# Occupancy_PCB_Final_Rev_B.net
KiCad netlist of a schematic drawn in EAGLE
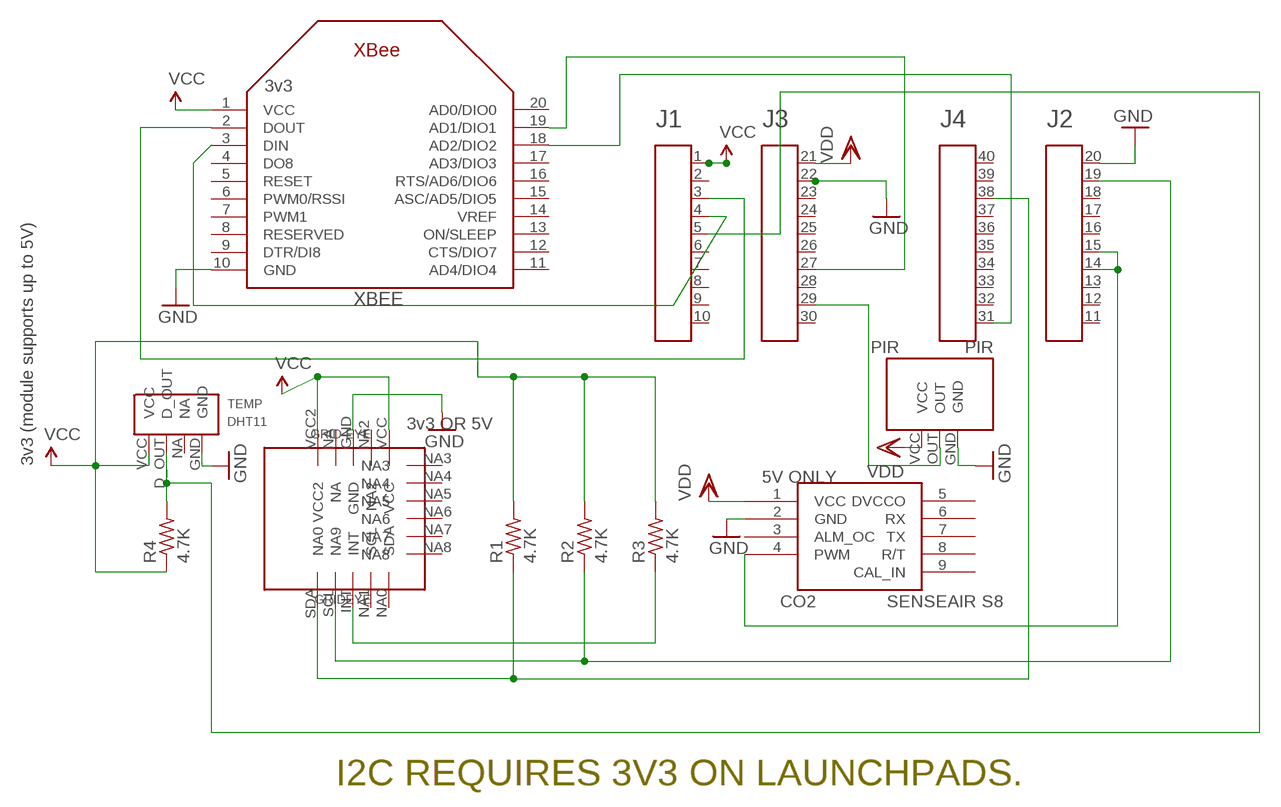
[diagram p0: schematic, sheet 1]

(export (version "E")
  (design (tool "Eeschema 10.0.6"))
  (components
    (comp (ref "CO2")
      (value "SENSEAIR-S8-DIP")
      (footprint "eagle-import:SENSEAIR-S8-DIP")
      (libsource (lib "eagle-import") (part "SENSEAIR-S8-DIP"))
    )
    (comp (ref "GRIDEYE")
      (value "GRID-EYE-DIP")
      (footprint "eagle-import:GRID-EYE-DIP")
      (libsource (lib "eagle-import") (part "GRID-EYE-DIP"))
    )
    (comp (ref "LAUNCHPAD")
      (value "HEADER4X10-BOOSTERPACK")
      (footprint "eagle-import:4X10-BOOSTERPACK")
      (libsource (lib "eagle-import") (part "HEADER4X10-BOOSTERPACK"))
    )
    (comp (ref "PIR")
      (value "PIR-DIP")
      (footprint "eagle-import:PIR-DIP")
      (libsource (lib "eagle-import") (part "PIR-DIP"))
    )
    (comp (ref "R1")
      (value "4.7K")
      (footprint "eagle-import:R0805")
      (libsource (lib "eagle-import") (part "R-US_R0805"))
    )
    (comp (ref "R2")
      (value "4.7K")
      (footprint "eagle-import:R0805")
      (libsource (lib "eagle-import") (part "R-US_R0805"))
    )
    (comp (ref "R3")
      (value "4.7K")
      (footprint "eagle-import:R0805")
      (libsource (lib "eagle-import") (part "R-US_R0805"))
    )
    (comp (ref "R4")
      (value "4.7K")
      (footprint "eagle-import:R0805")
      (libsource (lib "eagle-import") (part "R-US_R0805"))
    )
    (comp (ref "TEMP")
      (value "DHT11-DIP")
      (footprint "eagle-import:DHT11-DIP")
      (libsource (lib "eagle-import") (part "DHT11-DIP"))
    )
    (comp (ref "XBEE")
      (value "XBEE")
      (footprint "eagle-import:XBEE")
      (libsource (lib "eagle-import") (part "XBEE"))
    )
  )
  (nets
    (net (code "1") (name "GND") (class "Default")
      (node (ref "CO2") (pin "2") (pinfunction "GND_2") (pintype "bidirectional"))
      (node (ref "GRIDEYE") (pin "GND") (pinfunction "GND_GND") (pintype "bidirectional"))
      (node (ref "LAUNCHPAD") (pin "20") (pinfunction "P$20_20") (pintype "bidirectional"))
      (node (ref "LAUNCHPAD") (pin "22") (pinfunction "P$22_22") (pintype "bidirectional"))
      (node (ref "PIR") (pin "GND") (pinfunction "GND_GND") (pintype "bidirectional"))
      (node (ref "TEMP") (pin "GND") (pinfunction "GND_GND") (pintype "bidirectional"))
      (node (ref "XBEE") (pin "10") (pinfunction "GND_10") (pintype "power_in"))
    )
    (net (code "2") (name "Net-(CO2-PWM)") (class "Default")
      (node (ref "CO2") (pin "4") (pinfunction "PWM_4") (pintype "bidirectional"))
      (node (ref "LAUNCHPAD") (pin "14") (pinfunction "P$14_14") (pintype "bidirectional"))
      (node (ref "LAUNCHPAD") (pin "15") (pinfunction "P$15_15") (pintype "bidirectional"))
    )
    (net (code "3") (name "Net-(GRIDEYE-NA0)") (class "Default")
      (node (ref "GRIDEYE") (pin "SDA") (pinfunction "NA0_SDA") (pintype "bidirectional"))
      (node (ref "LAUNCHPAD") (pin "38") (pinfunction "P$38_38") (pintype "bidirectional"))
      (node (ref "R1") (pin "1") (pinfunction "1_1") (pintype "passive"))
    )
    (net (code "4") (name "Net-(GRIDEYE-NA9)") (class "Default")
      (node (ref "GRIDEYE") (pin "SCL") (pinfunction "NA9_SCL") (pintype "bidirectional"))
      (node (ref "LAUNCHPAD") (pin "19") (pinfunction "P$19_19") (pintype "bidirectional"))
      (node (ref "R2") (pin "1") (pinfunction "1_1") (pintype "passive"))
    )
    (net (code "5") (name "Net-(GRIDEYE-PadINT)") (class "Default")
      (node (ref "GRIDEYE") (pin "INT") (pinfunction "INT_INT") (pintype "bidirectional"))
      (node (ref "R3") (pin "1") (pinfunction "1_1") (pintype "passive"))
    )
    (net (code "6") (name "Net-(LAUNCHPAD-P$3)") (class "Default")
      (node (ref "LAUNCHPAD") (pin "3") (pinfunction "P$3_3") (pintype "bidirectional"))
      (node (ref "XBEE") (pin "2") (pinfunction "DOUT_2") (pintype "output"))
    )
    (net (code "7") (name "Net-(LAUNCHPAD-P$4)") (class "Default")
      (node (ref "LAUNCHPAD") (pin "4") (pinfunction "P$4_4") (pintype "bidirectional"))
      (node (ref "XBEE") (pin "3") (pinfunction "DIN_3") (pintype "input"))
    )
    (net (code "8") (name "Net-(LAUNCHPAD-P$5)") (class "Default")
      (node (ref "LAUNCHPAD") (pin "5") (pinfunction "P$5_5") (pintype "bidirectional"))
      (node (ref "R4") (pin "2") (pinfunction "2_2") (pintype "passive"))
      (node (ref "TEMP") (pin "D_OUT") (pinfunction "D_OUT_D_OUT") (pintype "bidirectional"))
    )
    (net (code "9") (name "Net-(LAUNCHPAD-P$27)") (class "Default")
      (node (ref "LAUNCHPAD") (pin "27") (pinfunction "P$27_27") (pintype "bidirectional"))
      (node (ref "XBEE") (pin "19") (pinfunction "AD1/DIO1_19") (pintype "bidirectional"))
    )
    (net (code "10") (name "Net-(LAUNCHPAD-P$29)") (class "Default")
      (node (ref "LAUNCHPAD") (pin "29") (pinfunction "P$29_29") (pintype "bidirectional"))
      (node (ref "PIR") (pin "OUT") (pinfunction "OUT_OUT") (pintype "bidirectional"))
    )
    (net (code "11") (name "Net-(LAUNCHPAD-P$31)") (class "Default")
      (node (ref "LAUNCHPAD") (pin "31") (pinfunction "P$31_31") (pintype "bidirectional"))
      (node (ref "XBEE") (pin "18") (pinfunction "AD2/DIO2_18") (pintype "bidirectional"))
    )
    (net (code "12") (name "VCC") (class "Default")
      (node (ref "GRIDEYE") (pin "VCC") (pinfunction "VCC_VCC") (pintype "bidirectional"))
      (node (ref "GRIDEYE") (pin "VCC2") (pinfunction "VCC2_VCC2") (pintype "bidirectional"))
      (node (ref "LAUNCHPAD") (pin "1") (pinfunction "P$1_1") (pintype "bidirectional"))
      (node (ref "R1") (pin "2") (pinfunction "2_2") (pintype "passive"))
      (node (ref "R2") (pin "2") (pinfunction "2_2") (pintype "passive"))
      (node (ref "R3") (pin "2") (pinfunction "2_2") (pintype "passive"))
      (node (ref "R4") (pin "1") (pinfunction "1_1") (pintype "passive"))
      (node (ref "TEMP") (pin "VCC") (pinfunction "VCC_VCC") (pintype "bidirectional"))
      (node (ref "XBEE") (pin "1") (pinfunction "VCC_1") (pintype "power_in"))
    )
    (net (code "13") (name "VDD") (class "Default")
      (node (ref "CO2") (pin "1") (pinfunction "VCC_1") (pintype "bidirectional"))
      (node (ref "LAUNCHPAD") (pin "21") (pinfunction "P$21_21") (pintype "bidirectional"))
      (node (ref "PIR") (pin "VCC") (pinfunction "VCC_VCC") (pintype "bidirectional"))
    )
    (net (code "14") (name "unconnected-(CO2-ALM_OC-Pad3)") (class "Default")
      (node (ref "CO2") (pin "3") (pinfunction "ALM_OC_3") (pintype "bidirectional"))
    )
    (net (code "15") (name "unconnected-(CO2-CAL_IN-Pad9)") (class "Default")
      (node (ref "CO2") (pin "9") (pinfunction "CAL_IN_9") (pintype "bidirectional"))
    )
    (net (code "16") (name "unconnected-(CO2-DVCCO-Pad5)") (class "Default")
      (node (ref "CO2") (pin "5") (pinfunction "DVCCO_5") (pintype "bidirectional"))
    )
    (net (code "17") (name "unconnected-(CO2-RX-Pad6)") (class "Default")
      (node (ref "CO2") (pin "6") (pinfunction "RX_6") (pintype "bidirectional"))
    )
    (net (code "18") (name "unconnected-(CO2-R{slash}T-Pad8)") (class "Default")
      (node (ref "CO2") (pin "8") (pinfunction "R/T_8") (pintype "bidirectional"))
    )
    (net (code "19") (name "unconnected-(CO2-TX-Pad7)") (class "Default")
      (node (ref "CO2") (pin "7") (pinfunction "TX_7") (pintype "bidirectional"))
    )
    (net (code "20") (name "unconnected-(GRIDEYE-PadNA)") (class "Default")
      (node (ref "GRIDEYE") (pin "NA") (pinfunction "NA_NA") (pintype "bidirectional"))
    )
    (net (code "21") (name "unconnected-(GRIDEYE-PadNA2)") (class "Default")
      (node (ref "GRIDEYE") (pin "NA2") (pinfunction "NA2_NA2") (pintype "bidirectional"))
    )
    (net (code "22") (name "unconnected-(GRIDEYE-PadNA3)") (class "Default")
      (node (ref "GRIDEYE") (pin "NA3") (pinfunction "NA3_NA3") (pintype "bidirectional"))
    )
    (net (code "23") (name "unconnected-(GRIDEYE-PadNA4)") (class "Default")
      (node (ref "GRIDEYE") (pin "NA4") (pinfunction "NA4_NA4") (pintype "bidirectional"))
    )
    (net (code "24") (name "unconnected-(GRIDEYE-PadNA5)") (class "Default")
      (node (ref "GRIDEYE") (pin "NA5") (pinfunction "NA5_NA5") (pintype "bidirectional"))
    )
    (net (code "25") (name "unconnected-(GRIDEYE-PadNA6)") (class "Default")
      (node (ref "GRIDEYE") (pin "NA6") (pinfunction "NA6_NA6") (pintype "bidirectional"))
    )
    (net (code "26") (name "unconnected-(GRIDEYE-PadNA7)") (class "Default")
      (node (ref "GRIDEYE") (pin "NA7") (pinfunction "NA7_NA7") (pintype "bidirectional"))
    )
    (net (code "27") (name "unconnected-(GRIDEYE-PadNA8)") (class "Default")
      (node (ref "GRIDEYE") (pin "NA8") (pinfunction "NA8_NA8") (pintype "bidirectional"))
    )
    (net (code "28") (name "unconnected-(GRIDEYE-SCL-PadNA1)") (class "Default")
      (node (ref "GRIDEYE") (pin "NA1") (pinfunction "SCL_NA1") (pintype "bidirectional"))
    )
    (net (code "29") (name "unconnected-(GRIDEYE-SDA-PadNA0)") (class "Default")
      (node (ref "GRIDEYE") (pin "NA0") (pinfunction "SDA_NA0") (pintype "bidirectional"))
    )
    (net (code "30") (name "unconnected-(LAUNCHPAD-P$2-Pad2)") (class "Default")
      (node (ref "LAUNCHPAD") (pin "2") (pinfunction "P$2_2") (pintype "bidirectional"))
    )
    (net (code "31") (name "unconnected-(LAUNCHPAD-P$6-Pad6)") (class "Default")
      (node (ref "LAUNCHPAD") (pin "6") (pinfunction "P$6_6") (pintype "bidirectional"))
    )
    (net (code "32") (name "unconnected-(LAUNCHPAD-P$7-Pad7)") (class "Default")
      (node (ref "LAUNCHPAD") (pin "7") (pinfunction "P$7_7") (pintype "bidirectional"))
    )
    (net (code "33") (name "unconnected-(LAUNCHPAD-P$8-Pad8)") (class "Default")
      (node (ref "LAUNCHPAD") (pin "8") (pinfunction "P$8_8") (pintype "bidirectional"))
    )
    (net (code "34") (name "unconnected-(LAUNCHPAD-P$9-Pad9)") (class "Default")
      (node (ref "LAUNCHPAD") (pin "9") (pinfunction "P$9_9") (pintype "bidirectional"))
    )
    (net (code "35") (name "unconnected-(LAUNCHPAD-P$10-Pad10)") (class "Default")
      (node (ref "LAUNCHPAD") (pin "10") (pinfunction "P$10_10") (pintype "bidirectional"))
    )
    (net (code "36") (name "unconnected-(LAUNCHPAD-P$11-Pad11)") (class "Default")
      (node (ref "LAUNCHPAD") (pin "11") (pinfunction "P$11_11") (pintype "bidirectional"))
    )
    (net (code "37") (name "unconnected-(LAUNCHPAD-P$12-Pad12)") (class "Default")
      (node (ref "LAUNCHPAD") (pin "12") (pinfunction "P$12_12") (pintype "bidirectional"))
    )
    (net (code "38") (name "unconnected-(LAUNCHPAD-P$13-Pad13)") (class "Default")
      (node (ref "LAUNCHPAD") (pin "13") (pinfunction "P$13_13") (pintype "bidirectional"))
    )
    (net (code "39") (name "unconnected-(LAUNCHPAD-P$16-Pad16)") (class "Default")
      (node (ref "LAUNCHPAD") (pin "16") (pinfunction "P$16_16") (pintype "bidirectional"))
    )
    (net (code "40") (name "unconnected-(LAUNCHPAD-P$17-Pad17)") (class "Default")
      (node (ref "LAUNCHPAD") (pin "17") (pinfunction "P$17_17") (pintype "bidirectional"))
    )
    (net (code "41") (name "unconnected-(LAUNCHPAD-P$18-Pad18)") (class "Default")
      (node (ref "LAUNCHPAD") (pin "18") (pinfunction "P$18_18") (pintype "bidirectional"))
    )
    (net (code "42") (name "unconnected-(LAUNCHPAD-P$23-Pad23)") (class "Default")
      (node (ref "LAUNCHPAD") (pin "23") (pinfunction "P$23_23") (pintype "bidirectional"))
    )
    (net (code "43") (name "unconnected-(LAUNCHPAD-P$24-Pad24)") (class "Default")
      (node (ref "LAUNCHPAD") (pin "24") (pinfunction "P$24_24") (pintype "bidirectional"))
    )
    (net (code "44") (name "unconnected-(LAUNCHPAD-P$25-Pad25)") (class "Default")
      (node (ref "LAUNCHPAD") (pin "25") (pinfunction "P$25_25") (pintype "bidirectional"))
    )
    (net (code "45") (name "unconnected-(LAUNCHPAD-P$26-Pad26)") (class "Default")
      (node (ref "LAUNCHPAD") (pin "26") (pinfunction "P$26_26") (pintype "bidirectional"))
    )
    (net (code "46") (name "unconnected-(LAUNCHPAD-P$28-Pad28)") (class "Default")
      (node (ref "LAUNCHPAD") (pin "28") (pinfunction "P$28_28") (pintype "bidirectional"))
    )
    (net (code "47") (name "unconnected-(LAUNCHPAD-P$30-Pad30)") (class "Default")
      (node (ref "LAUNCHPAD") (pin "30") (pinfunction "P$30_30") (pintype "bidirectional"))
    )
    (net (code "48") (name "unconnected-(LAUNCHPAD-P$32-Pad32)") (class "Default")
      (node (ref "LAUNCHPAD") (pin "32") (pinfunction "P$32_32") (pintype "bidirectional"))
    )
    (net (code "49") (name "unconnected-(LAUNCHPAD-P$33-Pad33)") (class "Default")
      (node (ref "LAUNCHPAD") (pin "33") (pinfunction "P$33_33") (pintype "bidirectional"))
    )
    (net (code "50") (name "unconnected-(LAUNCHPAD-P$34-Pad34)") (class "Default")
      (node (ref "LAUNCHPAD") (pin "34") (pinfunction "P$34_34") (pintype "bidirectional"))
    )
    (net (code "51") (name "unconnected-(LAUNCHPAD-P$35-Pad35)") (class "Default")
      (node (ref "LAUNCHPAD") (pin "35") (pinfunction "P$35_35") (pintype "bidirectional"))
    )
    (net (code "52") (name "unconnected-(LAUNCHPAD-P$36-Pad36)") (class "Default")
      (node (ref "LAUNCHPAD") (pin "36") (pinfunction "P$36_36") (pintype "bidirectional"))
    )
    (net (code "53") (name "unconnected-(LAUNCHPAD-P$37-Pad37)") (class "Default")
      (node (ref "LAUNCHPAD") (pin "37") (pinfunction "P$37_37") (pintype "bidirectional"))
    )
    (net (code "54") (name "unconnected-(LAUNCHPAD-P$39-Pad39)") (class "Default")
      (node (ref "LAUNCHPAD") (pin "39") (pinfunction "P$39_39") (pintype "bidirectional"))
    )
    (net (code "55") (name "unconnected-(LAUNCHPAD-P$40-Pad40)") (class "Default")
      (node (ref "LAUNCHPAD") (pin "40") (pinfunction "P$40_40") (pintype "bidirectional"))
    )
    (net (code "56") (name "unconnected-(TEMP-PadNA)") (class "Default")
      (node (ref "TEMP") (pin "NA") (pinfunction "NA_NA") (pintype "bidirectional"))
    )
    (net (code "57") (name "unconnected-(XBEE-AD0{slash}DIO0-Pad20)") (class "Default")
      (node (ref "XBEE") (pin "20") (pinfunction "AD0/DIO0_20") (pintype "bidirectional"))
    )
    (net (code "58") (name "unconnected-(XBEE-AD3{slash}DIO3-Pad17)") (class "Default")
      (node (ref "XBEE") (pin "17") (pinfunction "AD3/DIO3_17") (pintype "bidirectional"))
    )
    (net (code "59") (name "unconnected-(XBEE-AD4{slash}DIO4-Pad11)") (class "Default")
      (node (ref "XBEE") (pin "11") (pinfunction "AD4/DIO4_11") (pintype "bidirectional"))
    )
    (net (code "60") (name "unconnected-(XBEE-ASC{slash}AD5{slash}DIO5-Pad15)") (class "Default")
      (node (ref "XBEE") (pin "15") (pinfunction "ASC/AD5/DIO5_15") (pintype "bidirectional"))
    )
    (net (code "61") (name "unconnected-(XBEE-CTS{slash}DIO7-Pad12)") (class "Default")
      (node (ref "XBEE") (pin "12") (pinfunction "CTS/DIO7_12") (pintype "bidirectional"))
    )
    (net (code "62") (name "unconnected-(XBEE-DO8-Pad4)") (class "Default")
      (node (ref "XBEE") (pin "4") (pinfunction "DO8_4") (pintype "output"))
    )
    (net (code "63") (name "unconnected-(XBEE-DTR{slash}DI8-Pad9)") (class "Default")
      (node (ref "XBEE") (pin "9") (pinfunction "DTR/DI8_9") (pintype "input"))
    )
    (net (code "64") (name "unconnected-(XBEE-ON{slash}SLEEP-Pad13)") (class "Default")
      (node (ref "XBEE") (pin "13") (pinfunction "ON/SLEEP_13") (pintype "output"))
    )
    (net (code "65") (name "unconnected-(XBEE-PWM0{slash}RSSI-Pad6)") (class "Default")
      (node (ref "XBEE") (pin "6") (pinfunction "PWM0/RSSI_6") (pintype "output"))
    )
    (net (code "66") (name "unconnected-(XBEE-PWM1-Pad7)") (class "Default")
      (node (ref "XBEE") (pin "7") (pinfunction "PWM1_7") (pintype "output"))
    )
    (net (code "67") (name "unconnected-(XBEE-RESERVED-Pad8)") (class "Default")
      (node (ref "XBEE") (pin "8") (pinfunction "RESERVED_8") (pintype "no_connect"))
    )
    (net (code "68") (name "unconnected-(XBEE-RESET-Pad5)") (class "Default")
      (node (ref "XBEE") (pin "5") (pinfunction "RESET_5") (pintype "input"))
    )
    (net (code "69") (name "unconnected-(XBEE-RTS{slash}AD6{slash}DIO6-Pad16)") (class "Default")
      (node (ref "XBEE") (pin "16") (pinfunction "RTS/AD6/DIO6_16") (pintype "bidirectional"))
    )
    (net (code "70") (name "unconnected-(XBEE-VREF-Pad14)") (class "Default")
      (node (ref "XBEE") (pin "14") (pinfunction "VREF_14") (pintype "input"))
    )
  )
)
